# lcd13264-module.net
KiCad netlist of a schematic drawn in EAGLE
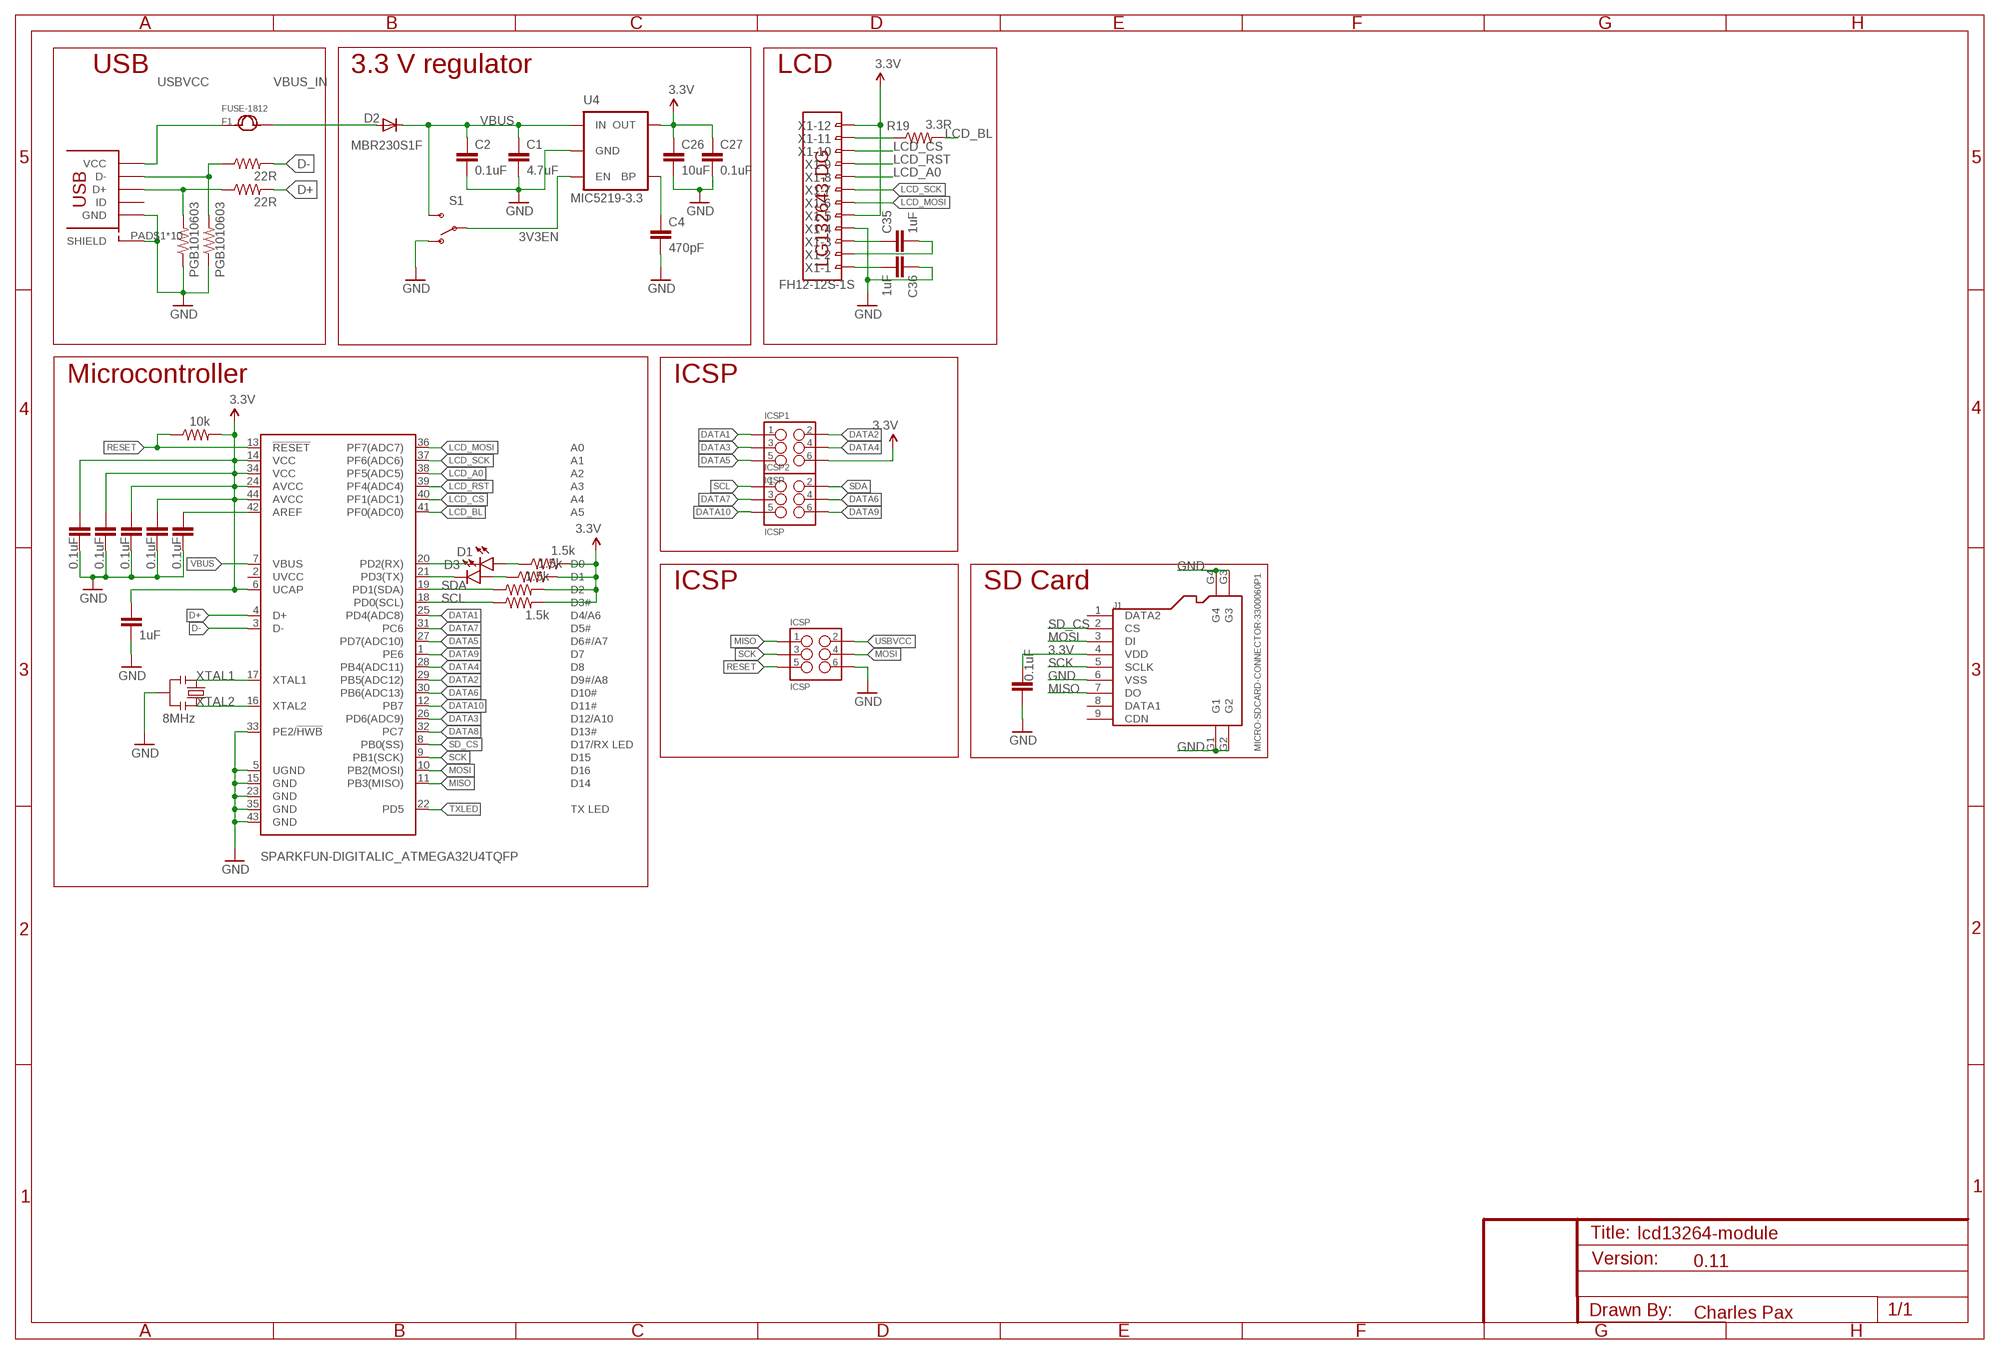
[diagram p0: schematic, sheet 1]

(export (version "E")
  (design (tool "Eeschema 10.0.6"))
  (components
    (comp (ref "C1")
      (value "4.7uF")
      (footprint "eagle-import:SPARKFUN-CAPACITORS_0603-CAP")
      (fields (field (name "MPN") "GRM188R60J475KE19D"))
      (libsource (lib "eagle-import") (part "SPARKFUN-CAPACITORS_CAP0603-CAP"))
    )
    (comp (ref "C2")
      (value "0.1uF")
      (footprint "eagle-import:SPARKFUN-CAPACITORS_0603-CAP")
      (fields (field (name "MPN") "CL10B104KO8NNNC"))
      (libsource (lib "eagle-import") (part "SPARKFUN-CAPACITORS_CAP0603-CAP"))
    )
    (comp (ref "C3")
      (value "0.1uF")
      (footprint "eagle-import:SPARKFUN-CAPACITORS_0603-CAP")
      (fields (field (name "MPN") "CL10B104KO8NNNC"))
      (libsource (lib "eagle-import") (part "SPARKFUN-CAPACITORS_CAP0603-CAP"))
    )
    (comp (ref "C4")
      (value "470pF")
      (footprint "eagle-import:SPARKFUN-CAPACITORS_0603-CAP")
      (fields (field (name "MPN") "C1608X5R1A474K080AA"))
      (libsource (lib "eagle-import") (part "SPARKFUN-CAPACITORS_CAP0603-CAP"))
    )
    (comp (ref "C5")
      (value "0.1uF")
      (footprint "eagle-import:SPARKFUN-CAPACITORS_0603-CAP")
      (fields (field (name "MPN") "CL10B104KO8NNNC"))
      (libsource (lib "eagle-import") (part "SPARKFUN-CAPACITORS_CAP0603-CAP"))
    )
    (comp (ref "C19")
      (value "1uF")
      (footprint "eagle-import:SPARKFUN-CAPACITORS_0603-CAP")
      (fields (field (name "MPN") "LMK107B7105KA-T"))
      (libsource (lib "eagle-import") (part "SPARKFUN-CAPACITORS_CAP0603-CAP"))
    )
    (comp (ref "C21")
      (value "0.1uF")
      (footprint "eagle-import:SPARKFUN-CAPACITORS_0603-CAP")
      (fields (field (name "MPN") "CL10B104KO8NNNC"))
      (libsource (lib "eagle-import") (part "SPARKFUN-CAPACITORS_CAP0603-CAP"))
    )
    (comp (ref "C26")
      (value "10uF")
      (footprint "eagle-import:SPARKFUN-CAPACITORS_0603-CAP")
      (fields (field (name "MPN") "JMK107ABJ106MAHT"))
      (libsource (lib "eagle-import") (part "SPARKFUN-CAPACITORS_CAP0603-CAP"))
    )
    (comp (ref "C27")
      (value "0.1uF")
      (footprint "eagle-import:SPARKFUN-CAPACITORS_0603-CAP")
      (fields (field (name "MPN") "CL10B104KO8NNNC"))
      (libsource (lib "eagle-import") (part "SPARKFUN-CAPACITORS_CAP0603-CAP"))
    )
    (comp (ref "C32")
      (value "0.1uF")
      (footprint "eagle-import:SPARKFUN-CAPACITORS_0603-CAP")
      (fields (field (name "MPN") "CL10B104KO8NNNC"))
      (libsource (lib "eagle-import") (part "SPARKFUN-CAPACITORS_CAP0603-CAP"))
    )
    (comp (ref "C33")
      (value "0.1uF")
      (footprint "eagle-import:SPARKFUN-CAPACITORS_0603-CAP")
      (fields (field (name "MPN") "CL10B104KO8NNNC"))
      (libsource (lib "eagle-import") (part "SPARKFUN-CAPACITORS_CAP0603-CAP"))
    )
    (comp (ref "C34")
      (value "0.1uF")
      (footprint "eagle-import:SPARKFUN-CAPACITORS_0603-CAP")
      (fields (field (name "MPN") "CL10B104KO8NNNC"))
      (libsource (lib "eagle-import") (part "SPARKFUN-CAPACITORS_CAP0603-CAP"))
    )
    (comp (ref "C35")
      (value "1uF")
      (footprint "eagle-import:SPARKFUN-CAPACITORS_0603-CAP")
      (fields (field (name "MPN") "LMK107B7105KA-T"))
      (libsource (lib "eagle-import") (part "SPARKFUN-CAPACITORS_CAP0603-CAP"))
    )
    (comp (ref "C36")
      (value "1uF")
      (footprint "eagle-import:SPARKFUN-CAPACITORS_0603-CAP")
      (fields (field (name "MPN") "LMK107B7105KA-T"))
      (libsource (lib "eagle-import") (part "SPARKFUN-CAPACITORS_CAP0603-CAP"))
    )
    (comp (ref "D1")
      (value "LED0603")
      (footprint "eagle-import:LED-0603")
      (libsource (lib "eagle-import") (part "LED0603"))
    )
    (comp (ref "D2")
      (value "MBR230S1F")
      (footprint "eagle-import:SOD123")
      (fields (field (name "MPN") "B340A-13-F"))
      (libsource (lib "eagle-import") (part "SPARKFUN-DISCRETESEMI_DIODESOD123SOD123"))
    )
    (comp (ref "D3")
      (value "LED0603")
      (footprint "eagle-import:LED-0603")
      (libsource (lib "eagle-import") (part "LED0603"))
    )
    (comp (ref "F1")
      (value "FUSE-1812")
      (footprint "eagle-import:F1812")
      (libsource (lib "eagle-import") (part "FUSE-1812"))
    )
    (comp (ref "ICSP")
      (value "ICSP")
      (footprint "eagle-import:SPARKFUN-CONNECTORS_2X3_SMT_POSTS_PAXINSTRUMENT")
      (fields (field (name "MPN") "95278-101A06LF"))
      (libsource (lib "eagle-import") (part "SPARKFUN-CONNECTORS_M03X2PAX"))
    )
    (comp (ref "ICSP1")
      (value "ICSP")
      (footprint "eagle-import:SPARKFUN-CONNECTORS_2X3_SMT_POSTS_PAXINSTRUMENT")
      (fields (field (name "MPN") "95278-101A06LF"))
      (libsource (lib "eagle-import") (part "SPARKFUN-CONNECTORS_M03X2PAX"))
    )
    (comp (ref "ICSP2")
      (value "ICSP")
      (footprint "eagle-import:SPARKFUN-CONNECTORS_2X3_SMT_POSTS_PAXINSTRUMENT")
      (fields (field (name "MPN") "95278-101A06LF"))
      (libsource (lib "eagle-import") (part "SPARKFUN-CONNECTORS_M03X2PAX"))
    )
    (comp (ref "J1")
      (value "MICRO-SDCARD-CONNECTOR-3300060P1")
      (footprint "eagle-import:9P-SMD-W-RING")
      (libsource (lib "eagle-import") (part "MICRO-SDCARD-CONNECTOR-3300060P1"))
    )
    (comp (ref "R1")
      (value "1.5k")
      (footprint "eagle-import:SPARKFUN-RESISTORS_0603-RES")
      (fields (field (name "MPN") "RC0603JR-071K5L"))
      (libsource (lib "eagle-import") (part "SPARKFUN-RESISTORS_RESISTOR0603-RES"))
    )
    (comp (ref "R2")
      (value "1.5k")
      (footprint "eagle-import:SPARKFUN-RESISTORS_0603-RES")
      (fields (field (name "MPN") "RC0603JR-071K5L"))
      (libsource (lib "eagle-import") (part "SPARKFUN-RESISTORS_RESISTOR0603-RES"))
    )
    (comp (ref "R4")
      (value "10k")
      (footprint "eagle-import:SPARKFUN-RESISTORS_0603-RES")
      (fields (field (name "MPN") "RC1608J103CS"))
      (libsource (lib "eagle-import") (part "SPARKFUN-RESISTORS_RESISTOR0603-RES"))
    )
    (comp (ref "R9")
      (value "22R")
      (footprint "eagle-import:SPARKFUN-RESISTORS_0603-RES")
      (fields (field (name "MPN") "RC0603JR-0722RL"))
      (libsource (lib "eagle-import") (part "SPARKFUN-RESISTORS_RESISTOR0603-RES"))
    )
    (comp (ref "R10")
      (value "22R")
      (footprint "eagle-import:SPARKFUN-RESISTORS_0603-RES")
      (fields (field (name "MPN") "RC0603JR-0722RL"))
      (libsource (lib "eagle-import") (part "SPARKFUN-RESISTORS_RESISTOR0603-RES"))
    )
    (comp (ref "R13")
      (value "1.5k")
      (footprint "eagle-import:SPARKFUN-RESISTORS_0603-RES")
      (fields (field (name "MPN") "RC0603JR-071K5L"))
      (libsource (lib "eagle-import") (part "SPARKFUN-RESISTORS_RESISTOR0603-RES"))
    )
    (comp (ref "R14")
      (value "1.5k")
      (footprint "eagle-import:SPARKFUN-RESISTORS_0603-RES")
      (fields (field (name "MPN") "RC0603JR-071K5L"))
      (libsource (lib "eagle-import") (part "SPARKFUN-RESISTORS_RESISTOR0603-RES"))
    )
    (comp (ref "R19")
      (value "3.3R")
      (footprint "eagle-import:SPARKFUN-RESISTORS_0603-RES")
      (libsource (lib "eagle-import") (part "SPARKFUN-RESISTORS_RESISTOR0603-RES"))
    )
    (comp (ref "S1")
      (value "SWITCH-SPDT-SMD-A")
      (footprint "eagle-import:SWITCH-SPST-SMD-A")
      (libsource (lib "eagle-import") (part "SWITCH-SPDT-SMD-A"))
    )
    (comp (ref "U$1")
      (value "USB_MICROSMT+THRUHULE")
      (footprint "eagle-import:USB_MICRO_THRUHOLE")
      (fields (field (name "MPN") "10118194-0001LF"))
      (libsource (lib "eagle-import") (part "USB_MICROSMT+THRUHULE"))
    )
    (comp (ref "U$3")
      (value "SPARKFUN-DIGITALIC_ATMEGA32U4TQFP")
      (footprint "eagle-import:SPARKFUN-DIGITALIC_SPARKFUN-DIGITALIC_TQFP44")
      (libsource (lib "eagle-import") (part "SPARKFUN-DIGITALIC_ATMEGA32U4TQFP"))
    )
    (comp (ref "U$5")
      (value "LG132643-DG")
      (footprint "eagle-import:LG132643-DG")
      (fields (field (name "MPN") "LG132643-DW"))
      (libsource (lib "eagle-import") (part "LG132643-DG"))
    )
    (comp (ref "U4")
      (value "MIC5219-3.3V")
      (footprint "eagle-import:SOT23-5")
      (fields (field (name "MPN") "MIC5219-3.3YM5 TR"))
      (libsource (lib "eagle-import") (part "V_REG_LDOSMD"))
    )
    (comp (ref "X1")
      (value "FH12-12S-1S")
      (footprint "eagle-import:FH12-12S-1SH")
      (libsource (lib "eagle-import") (part "FH12-12S-1S"))
    )
    (comp (ref "Y1")
      (value "RESONATORSMD")
      (footprint "eagle-import:RESONATOR-SMD")
      (fields (field (name "MPN") "CSTCE8M00G52-R0"))
      (libsource (lib "eagle-import") (part "RESONATORSMD"))
    )
    (comp (ref "Z1")
      (value "PGB1010603")
      (footprint "eagle-import:SPARKFUN-RESISTORS_0603-RES")
      (fields (field (name "MPN") "PGB1010603NRHF"))
      (libsource (lib "eagle-import") (part "SPARKFUN-RESISTORS_RESISTOR0603-RES"))
    )
    (comp (ref "Z2")
      (value "PGB1010603")
      (footprint "eagle-import:SPARKFUN-RESISTORS_0603-RES")
      (fields (field (name "MPN") "PGB1010603NRHF"))
      (libsource (lib "eagle-import") (part "SPARKFUN-RESISTORS_RESISTOR0603-RES"))
    )
  )
  (nets
    (net (code "1") (name "/3V3EN") (class "Default")
      (node (ref "S1") (pin "2") (pinfunction "P_2") (pintype "passive"))
      (node (ref "U4") (pin "3") (pinfunction "EN_3") (pintype "input"))
    )
    (net (code "2") (name "/VBUS_IN") (class "Default")
      (node (ref "D2") (pin "A") (pinfunction "A_A") (pintype "passive"))
      (node (ref "F1") (pin "2") (pinfunction "2_2") (pintype "bidirectional"))
    )
    (net (code "3") (name "/XTAL1") (class "Default")
      (node (ref "U$3") (pin "17") (pinfunction "XTAL1_17") (pintype "bidirectional"))
      (node (ref "Y1") (pin "1") (pinfunction "1_1") (pintype "passive"))
    )
    (net (code "4") (name "/XTAL2") (class "Default")
      (node (ref "U$3") (pin "16") (pinfunction "XTAL2_16") (pintype "bidirectional"))
      (node (ref "Y1") (pin "3") (pinfunction "3_3") (pintype "passive"))
    )
    (net (code "5") (name "3.3V") (class "Default")
      (node (ref "C19") (pin "1") (pinfunction "1_1") (pintype "passive"))
      (node (ref "C21") (pin "2") (pinfunction "2_2") (pintype "passive"))
      (node (ref "C26") (pin "1") (pinfunction "1_1") (pintype "passive"))
      (node (ref "C27") (pin "1") (pinfunction "1_1") (pintype "passive"))
      (node (ref "C32") (pin "1") (pinfunction "1_1") (pintype "passive"))
      (node (ref "C33") (pin "1") (pinfunction "1_1") (pintype "passive"))
      (node (ref "C34") (pin "1") (pinfunction "1_1") (pintype "passive"))
      (node (ref "C5") (pin "1") (pinfunction "1_1") (pintype "passive"))
      (node (ref "ICSP1") (pin "6") (pinfunction "6_6") (pintype "bidirectional"))
      (node (ref "J1") (pin "4") (pinfunction "VDD_4") (pintype "bidirectional"))
      (node (ref "R1") (pin "2") (pinfunction "2_2") (pintype "passive"))
      (node (ref "R13") (pin "2") (pinfunction "2_2") (pintype "passive"))
      (node (ref "R14") (pin "2") (pinfunction "2_2") (pintype "passive"))
      (node (ref "R2") (pin "2") (pinfunction "2_2") (pintype "passive"))
      (node (ref "R4") (pin "2") (pinfunction "2_2") (pintype "passive"))
      (node (ref "U$3") (pin "14") (pinfunction "VCC_14") (pintype "bidirectional"))
      (node (ref "U$3") (pin "24") (pinfunction "AVCC_24") (pintype "bidirectional"))
      (node (ref "U$3") (pin "34") (pinfunction "VCC_34") (pintype "bidirectional"))
      (node (ref "U$3") (pin "44") (pinfunction "AVCC_44") (pintype "bidirectional"))
      (node (ref "U$3") (pin "6") (pinfunction "UCAP_6") (pintype "bidirectional"))
      (node (ref "U4") (pin "5") (pinfunction "OUT_5") (pintype "passive"))
      (node (ref "X1") (pin "12") (pinfunction "1_12") (pintype "passive"))
      (node (ref "X1") (pin "5") (pinfunction "1_5") (pintype "passive"))
    )
    (net (code "6") (name "D+") (class "Default")
      (node (ref "R9") (pin "2") (pinfunction "2_2") (pintype "passive"))
      (node (ref "U$3") (pin "4") (pinfunction "D+_4") (pintype "bidirectional"))
    )
    (net (code "7") (name "D-") (class "Default")
      (node (ref "R10") (pin "2") (pinfunction "2_2") (pintype "passive"))
      (node (ref "U$3") (pin "3") (pinfunction "D-_3") (pintype "bidirectional"))
    )
    (net (code "8") (name "DATA1") (class "Default")
      (node (ref "ICSP1") (pin "1") (pinfunction "1_1") (pintype "bidirectional"))
      (node (ref "U$3") (pin "25") (pinfunction "PD4(ADC8)_25") (pintype "bidirectional"))
    )
    (net (code "9") (name "DATA2") (class "Default")
      (node (ref "ICSP1") (pin "2") (pinfunction "2_2") (pintype "bidirectional"))
      (node (ref "U$3") (pin "29") (pinfunction "PB5(ADC12)_29") (pintype "bidirectional"))
    )
    (net (code "10") (name "DATA3") (class "Default")
      (node (ref "ICSP1") (pin "3") (pinfunction "3_3") (pintype "bidirectional"))
      (node (ref "U$3") (pin "26") (pinfunction "PD6(ADC9)_26") (pintype "bidirectional"))
    )
    (net (code "11") (name "DATA4") (class "Default")
      (node (ref "ICSP1") (pin "4") (pinfunction "4_4") (pintype "bidirectional"))
      (node (ref "U$3") (pin "28") (pinfunction "PB4(ADC11)_28") (pintype "bidirectional"))
    )
    (net (code "12") (name "DATA5") (class "Default")
      (node (ref "ICSP1") (pin "5") (pinfunction "5_5") (pintype "bidirectional"))
      (node (ref "U$3") (pin "27") (pinfunction "PD7(ADC10)_27") (pintype "bidirectional"))
    )
    (net (code "13") (name "DATA6") (class "Default")
      (node (ref "ICSP2") (pin "4") (pinfunction "4_4") (pintype "bidirectional"))
      (node (ref "U$3") (pin "30") (pinfunction "PB6(ADC13)_30") (pintype "bidirectional"))
    )
    (net (code "14") (name "DATA7") (class "Default")
      (node (ref "ICSP2") (pin "3") (pinfunction "3_3") (pintype "bidirectional"))
      (node (ref "U$3") (pin "31") (pinfunction "PC6_31") (pintype "bidirectional"))
    )
    (net (code "15") (name "DATA8") (class "Default")
      (node (ref "U$3") (pin "32") (pinfunction "PC7_32") (pintype "bidirectional"))
    )
    (net (code "16") (name "DATA9") (class "Default")
      (node (ref "ICSP2") (pin "6") (pinfunction "6_6") (pintype "bidirectional"))
      (node (ref "U$3") (pin "1") (pinfunction "PE6_1") (pintype "bidirectional"))
    )
    (net (code "17") (name "DATA10") (class "Default")
      (node (ref "ICSP2") (pin "5") (pinfunction "5_5") (pintype "bidirectional"))
      (node (ref "U$3") (pin "12") (pinfunction "PB7_12") (pintype "bidirectional"))
    )
    (net (code "18") (name "GND") (class "Default")
      (node (ref "C1") (pin "2") (pinfunction "2_2") (pintype "passive"))
      (node (ref "C19") (pin "2") (pinfunction "2_2") (pintype "passive"))
      (node (ref "C2") (pin "2") (pinfunction "2_2") (pintype "passive"))
      (node (ref "C21") (pin "1") (pinfunction "1_1") (pintype "passive"))
      (node (ref "C26") (pin "2") (pinfunction "2_2") (pintype "passive"))
      (node (ref "C27") (pin "2") (pinfunction "2_2") (pintype "passive"))
      (node (ref "C3") (pin "2") (pinfunction "2_2") (pintype "passive"))
      (node (ref "C32") (pin "2") (pinfunction "2_2") (pintype "passive"))
      (node (ref "C33") (pin "2") (pinfunction "2_2") (pintype "passive"))
      (node (ref "C34") (pin "2") (pinfunction "2_2") (pintype "passive"))
      (node (ref "C36") (pin "1") (pinfunction "1_1") (pintype "passive"))
      (node (ref "C4") (pin "2") (pinfunction "2_2") (pintype "passive"))
      (node (ref "C5") (pin "2") (pinfunction "2_2") (pintype "passive"))
      (node (ref "ICSP") (pin "6") (pinfunction "6_6") (pintype "bidirectional"))
      (node (ref "J1") (pin "6") (pinfunction "VSS_6") (pintype "bidirectional"))
      (node (ref "J1") (pin "G1") (pinfunction "G1_G1") (pintype "bidirectional"))
      (node (ref "J1") (pin "G2") (pinfunction "G2_G2") (pintype "bidirectional"))
      (node (ref "J1") (pin "G3") (pinfunction "G3_G3") (pintype "bidirectional"))
      (node (ref "J1") (pin "G4") (pinfunction "G4_G4") (pintype "bidirectional"))
      (node (ref "S1") (pin "1") (pinfunction "O_1") (pintype "passive"))
      (node (ref "U$1") (pin "PAD$1") (pinfunction "SHIELD_PAD$1") (pintype "bidirectional"))
      (node (ref "U$1") (pin "PAD$10") (pinfunction "SHIELD_PAD$10") (pintype "bidirectional"))
      (node (ref "U$1") (pin "PAD$2") (pinfunction "SHIELD_PAD$2") (pintype "bidirectional"))
      (node (ref "U$1") (pin "PAD$3") (pinfunction "SHIELD_PAD$3") (pintype "bidirectional"))
      (node (ref "U$1") (pin "PAD$4") (pinfunction "SHIELD_PAD$4") (pintype "bidirectional"))
      (node (ref "U$1") (pin "PAD$5") (pinfunction "SHIELD_PAD$5") (pintype "bidirectional"))
      (node (ref "U$1") (pin "PAD$6") (pinfunction "SHIELD_PAD$6") (pintype "bidirectional"))
      (node (ref "U$1") (pin "PAD$7") (pinfunction "SHIELD_PAD$7") (pintype "bidirectional"))
      (node (ref "U$1") (pin "PAD$8") (pinfunction "SHIELD_PAD$8") (pintype "bidirectional"))
      (node (ref "U$1") (pin "PAD$9") (pinfunction "SHIELD_PAD$9") (pintype "bidirectional"))
      (node (ref "U$1") (pin "PIN$5") (pinfunction "GND_PIN$5") (pintype "bidirectional"))
      (node (ref "U$3") (pin "15") (pinfunction "GND_15") (pintype "bidirectional"))
      (node (ref "U$3") (pin "23") (pinfunction "GND_23") (pintype "bidirectional"))
      (node (ref "U$3") (pin "33") (pinfunction "PE2/~{HWB}_33") (pintype "bidirectional"))
      (node (ref "U$3") (pin "35") (pinfunction "GND_35") (pintype "bidirectional"))
      (node (ref "U$3") (pin "43") (pinfunction "GND_43") (pintype "bidirectional"))
      (node (ref "U$3") (pin "5") (pinfunction "UGND_5") (pintype "bidirectional"))
      (node (ref "U4") (pin "2") (pinfunction "GND_2") (pintype "input"))
      (node (ref "X1") (pin "4") (pinfunction "1_4") (pintype "passive"))
      (node (ref "Y1") (pin "2") (pinfunction "2_2") (pintype "passive"))
      (node (ref "Z1") (pin "1") (pinfunction "1_1") (pintype "passive"))
      (node (ref "Z2") (pin "1") (pinfunction "1_1") (pintype "passive"))
    )
    (net (code "19") (name "LCD_A0") (class "Default")
      (node (ref "U$3") (pin "38") (pinfunction "PF5(ADC5)_38") (pintype "bidirectional"))
      (node (ref "X1") (pin "8") (pinfunction "1_8") (pintype "passive"))
    )
    (net (code "20") (name "LCD_BL") (class "Default")
      (node (ref "R19") (pin "2") (pinfunction "2_2") (pintype "passive"))
      (node (ref "U$3") (pin "41") (pinfunction "PF0(ADC0)_41") (pintype "bidirectional"))
    )
    (net (code "21") (name "LCD_CS") (class "Default")
      (node (ref "U$3") (pin "40") (pinfunction "PF1(ADC1)_40") (pintype "bidirectional"))
      (node (ref "X1") (pin "10") (pinfunction "1_10") (pintype "passive"))
    )
    (net (code "22") (name "LCD_MOSI") (class "Default")
      (node (ref "U$3") (pin "36") (pinfunction "PF7(ADC7)_36") (pintype "bidirectional"))
      (node (ref "X1") (pin "6") (pinfunction "1_6") (pintype "passive"))
    )
    (net (code "23") (name "LCD_RST") (class "Default")
      (node (ref "U$3") (pin "39") (pinfunction "PF4(ADC4)_39") (pintype "bidirectional"))
      (node (ref "X1") (pin "9") (pinfunction "1_9") (pintype "passive"))
    )
    (net (code "24") (name "LCD_SCK") (class "Default")
      (node (ref "U$3") (pin "37") (pinfunction "PF6(ADC6)_37") (pintype "bidirectional"))
      (node (ref "X1") (pin "7") (pinfunction "1_7") (pintype "passive"))
    )
    (net (code "25") (name "MISO") (class "Default")
      (node (ref "ICSP") (pin "1") (pinfunction "1_1") (pintype "bidirectional"))
      (node (ref "J1") (pin "7") (pinfunction "DO_7") (pintype "bidirectional"))
      (node (ref "U$3") (pin "11") (pinfunction "PB3(MISO)_11") (pintype "bidirectional"))
    )
    (net (code "26") (name "MOSI") (class "Default")
      (node (ref "ICSP") (pin "4") (pinfunction "4_4") (pintype "bidirectional"))
      (node (ref "J1") (pin "3") (pinfunction "DI_3") (pintype "bidirectional"))
      (node (ref "U$3") (pin "10") (pinfunction "PB2(MOSI)_10") (pintype "bidirectional"))
    )
    (net (code "27") (name "Net-(C36-Pad2)") (class "Default")
      (node (ref "C36") (pin "2") (pinfunction "2_2") (pintype "passive"))
      (node (ref "X1") (pin "1") (pinfunction "1_1") (pintype "passive"))
    )
    (net (code "28") (name "Net-(D1-PadA)") (class "Default")
      (node (ref "D1") (pin "A") (pinfunction "A_A") (pintype "passive"))
      (node (ref "R2") (pin "1") (pinfunction "1_1") (pintype "passive"))
    )
    (net (code "29") (name "Net-(D3-PadA)") (class "Default")
      (node (ref "D3") (pin "A") (pinfunction "A_A") (pintype "passive"))
      (node (ref "R1") (pin "1") (pinfunction "1_1") (pintype "passive"))
    )
    (net (code "30") (name "Net-(U$1-D+)") (class "Default")
      (node (ref "R9") (pin "1") (pinfunction "1_1") (pintype "passive"))
      (node (ref "U$1") (pin "PIN$3") (pinfunction "D+_PIN$3") (pintype "bidirectional"))
      (node (ref "Z1") (pin "2") (pinfunction "2_2") (pintype "passive"))
    )
    (net (code "31") (name "Net-(U$1-D-)") (class "Default")
      (node (ref "R10") (pin "1") (pinfunction "1_1") (pintype "passive"))
      (node (ref "U$1") (pin "PIN$2") (pinfunction "D-_PIN$2") (pintype "bidirectional"))
      (node (ref "Z2") (pin "2") (pinfunction "2_2") (pintype "passive"))
    )
    (net (code "32") (name "Net-(U$3-AREF)") (class "Default")
      (node (ref "C3") (pin "1") (pinfunction "1_1") (pintype "passive"))
      (node (ref "U$3") (pin "42") (pinfunction "AREF_42") (pintype "bidirectional"))
    )
    (net (code "33") (name "Net-(U$3-PD2(RX))") (class "Default")
      (node (ref "D1") (pin "C") (pinfunction "C_C") (pintype "passive"))
      (node (ref "U$3") (pin "20") (pinfunction "PD2(RX)_20") (pintype "bidirectional"))
    )
    (net (code "34") (name "Net-(U$3-PD3(TX))") (class "Default")
      (node (ref "D3") (pin "C") (pinfunction "C_C") (pintype "passive"))
      (node (ref "U$3") (pin "21") (pinfunction "PD3(TX)_21") (pintype "bidirectional"))
    )
    (net (code "35") (name "Net-(U4-BP)") (class "Default")
      (node (ref "C4") (pin "1") (pinfunction "1_1") (pintype "passive"))
      (node (ref "U4") (pin "4") (pinfunction "BP_4") (pintype "input"))
    )
    (net (code "36") (name "Net-(X1C-1)") (class "Default")
      (node (ref "R19") (pin "1") (pinfunction "1_1") (pintype "passive"))
      (node (ref "X1") (pin "11") (pinfunction "1_11") (pintype "passive"))
    )
    (net (code "37") (name "Net-(X1E-1)") (class "Default")
      (node (ref "C35") (pin "2") (pinfunction "2_2") (pintype "passive"))
      (node (ref "X1") (pin "2") (pinfunction "1_2") (pintype "passive"))
    )
    (net (code "38") (name "Net-(X1F-1)") (class "Default")
      (node (ref "C35") (pin "1") (pinfunction "1_1") (pintype "passive"))
      (node (ref "X1") (pin "3") (pinfunction "1_3") (pintype "passive"))
    )
    (net (code "39") (name "RESET") (class "Default")
      (node (ref "ICSP") (pin "5") (pinfunction "5_5") (pintype "bidirectional"))
      (node (ref "R4") (pin "1") (pinfunction "1_1") (pintype "passive"))
      (node (ref "U$3") (pin "13") (pinfunction "~{RESET}_13") (pintype "bidirectional"))
    )
    (net (code "40") (name "SCK") (class "Default")
      (node (ref "ICSP") (pin "3") (pinfunction "3_3") (pintype "bidirectional"))
      (node (ref "J1") (pin "5") (pinfunction "SCLK_5") (pintype "bidirectional"))
      (node (ref "U$3") (pin "9") (pinfunction "PB1(SCK)_9") (pintype "bidirectional"))
    )
    (net (code "41") (name "SCL") (class "Default")
      (node (ref "ICSP2") (pin "1") (pinfunction "1_1") (pintype "bidirectional"))
      (node (ref "R14") (pin "1") (pinfunction "1_1") (pintype "passive"))
      (node (ref "U$3") (pin "18") (pinfunction "PD0(SCL)_18") (pintype "bidirectional"))
    )
    (net (code "42") (name "SDA") (class "Default")
      (node (ref "ICSP2") (pin "2") (pinfunction "2_2") (pintype "bidirectional"))
      (node (ref "R13") (pin "1") (pinfunction "1_1") (pintype "passive"))
      (node (ref "U$3") (pin "19") (pinfunction "PD1(SDA)_19") (pintype "bidirectional"))
    )
    (net (code "43") (name "SD_CS") (class "Default")
      (node (ref "J1") (pin "2") (pinfunction "CS_2") (pintype "bidirectional"))
      (node (ref "U$3") (pin "8") (pinfunction "PB0(SS)_8") (pintype "bidirectional"))
    )
    (net (code "44") (name "TXLED") (class "Default")
      (node (ref "U$3") (pin "22") (pinfunction "PD5_22") (pintype "bidirectional"))
    )
    (net (code "45") (name "USBVCC") (class "Default")
      (node (ref "F1") (pin "1") (pinfunction "1_1") (pintype "bidirectional"))
      (node (ref "ICSP") (pin "2") (pinfunction "2_2") (pintype "bidirectional"))
      (node (ref "U$1") (pin "PIN$1") (pinfunction "VCC_PIN$1") (pintype "bidirectional"))
    )
    (net (code "46") (name "VBUS") (class "Default")
      (node (ref "C1") (pin "1") (pinfunction "1_1") (pintype "passive"))
      (node (ref "C2") (pin "1") (pinfunction "1_1") (pintype "passive"))
      (node (ref "D2") (pin "C") (pinfunction "C_C") (pintype "passive"))
      (node (ref "S1") (pin "3") (pinfunction "S_3") (pintype "passive"))
      (node (ref "U$3") (pin "7") (pinfunction "VBUS_7") (pintype "bidirectional"))
      (node (ref "U4") (pin "1") (pinfunction "IN_1") (pintype "input"))
    )
    (net (code "47") (name "unconnected-(J1-CDN-Pad9)") (class "Default")
      (node (ref "J1") (pin "9") (pinfunction "CDN_9") (pintype "bidirectional"))
    )
    (net (code "48") (name "unconnected-(J1-DATA1-Pad8)") (class "Default")
      (node (ref "J1") (pin "8") (pinfunction "DATA1_8") (pintype "bidirectional"))
    )
    (net (code "49") (name "unconnected-(J1-DATA2-Pad1)") (class "Default")
      (node (ref "J1") (pin "1") (pinfunction "DATA2_1") (pintype "bidirectional"))
    )
    (net (code "50") (name "unconnected-(U$1-ID-PadPIN$4)") (class "Default")
      (node (ref "U$1") (pin "PIN$4") (pinfunction "ID_PIN$4") (pintype "bidirectional"))
    )
    (net (code "51") (name "unconnected-(U$3-UVCC-Pad2)") (class "Default")
      (node (ref "U$3") (pin "2") (pinfunction "UVCC_2") (pintype "bidirectional"))
    )
  )
)
